# Input_Transceivers.net
KiCad netlist of a schematic drawn in Altium Designer
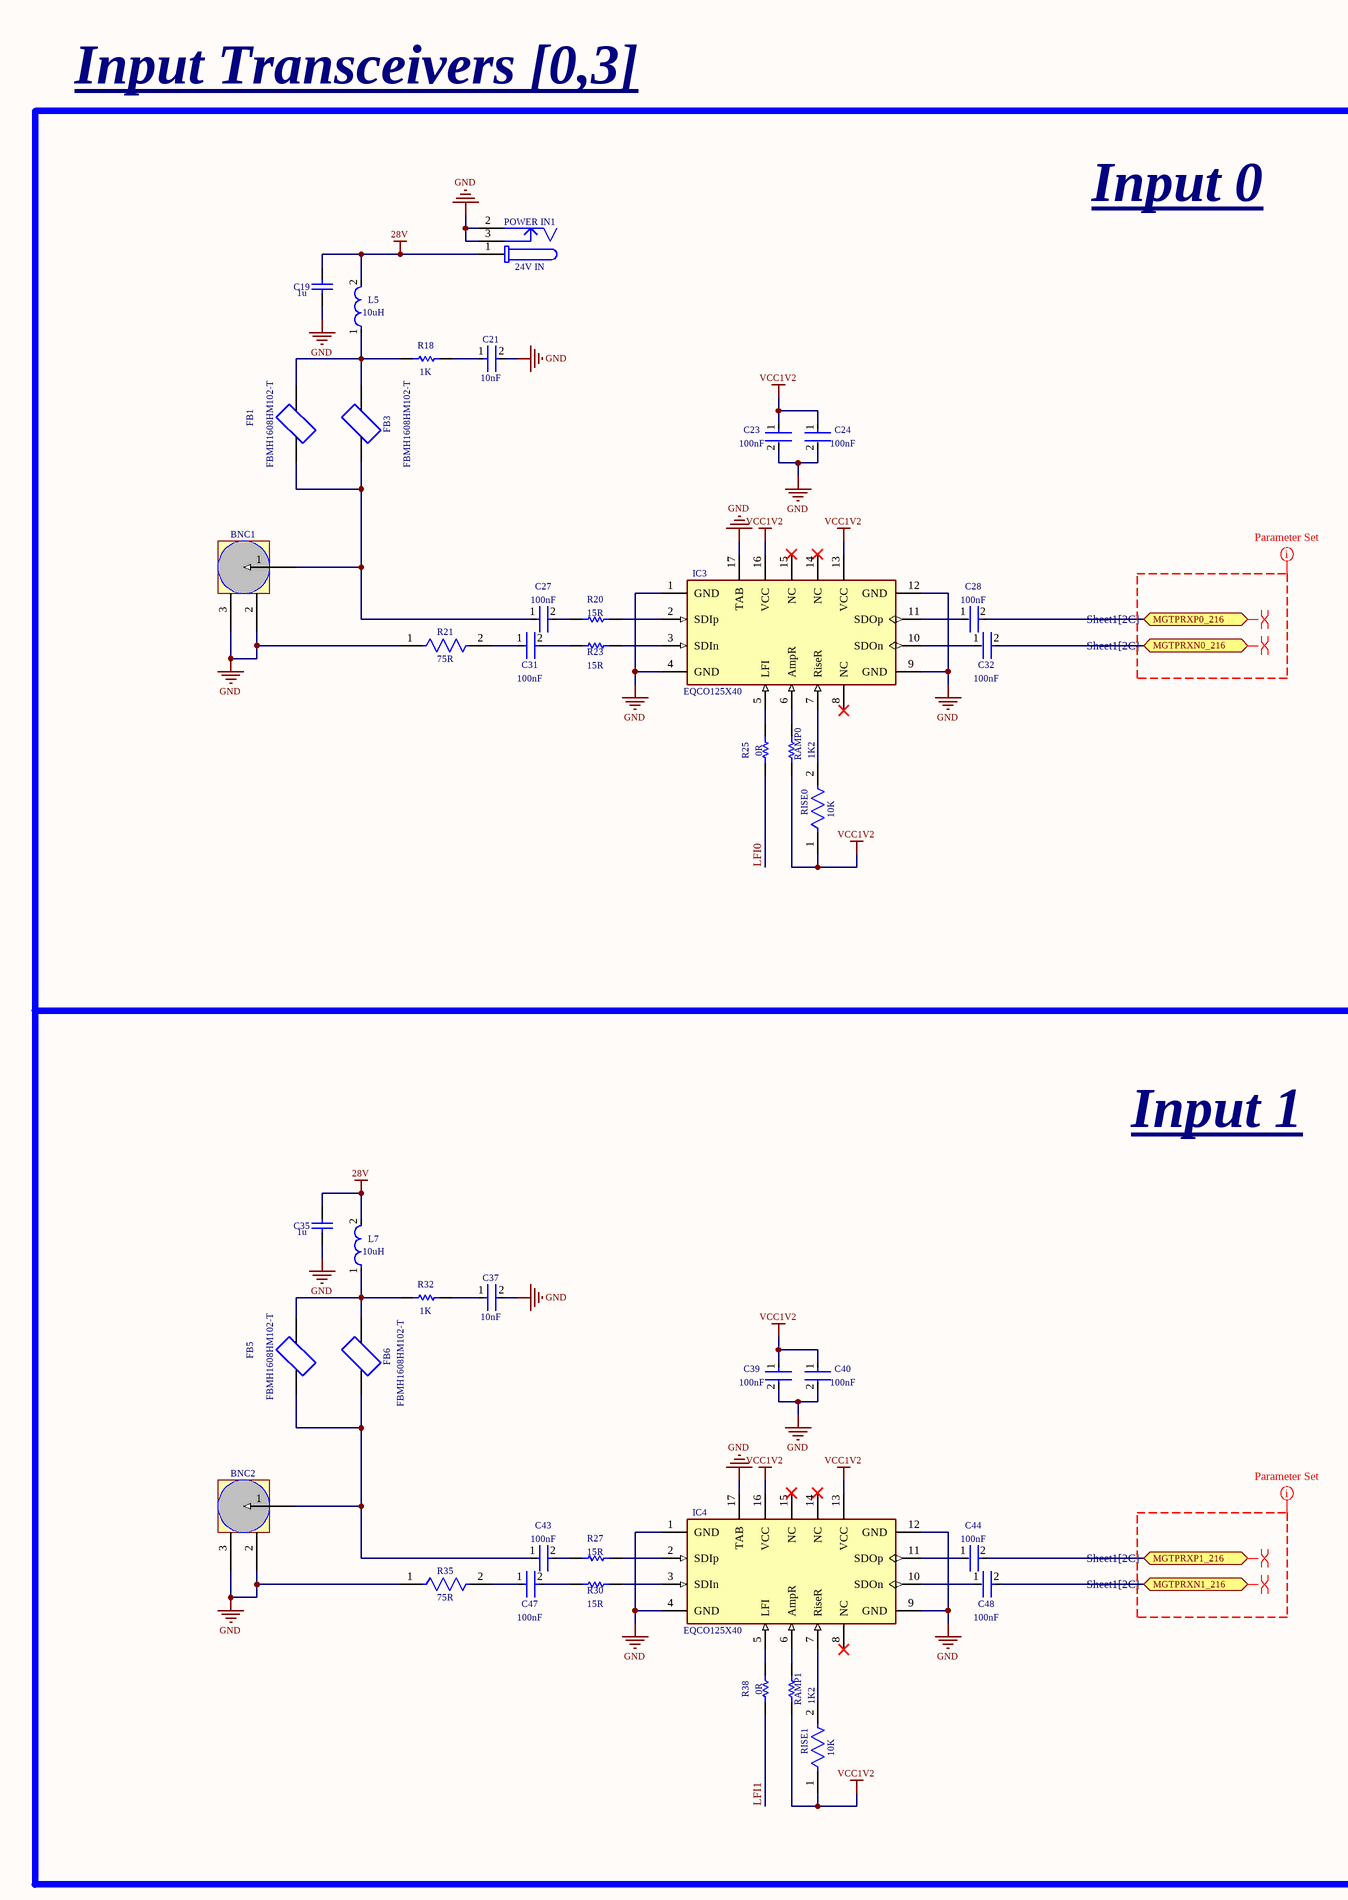
[diagram p0: Input Transceivers.SchDoc, left]
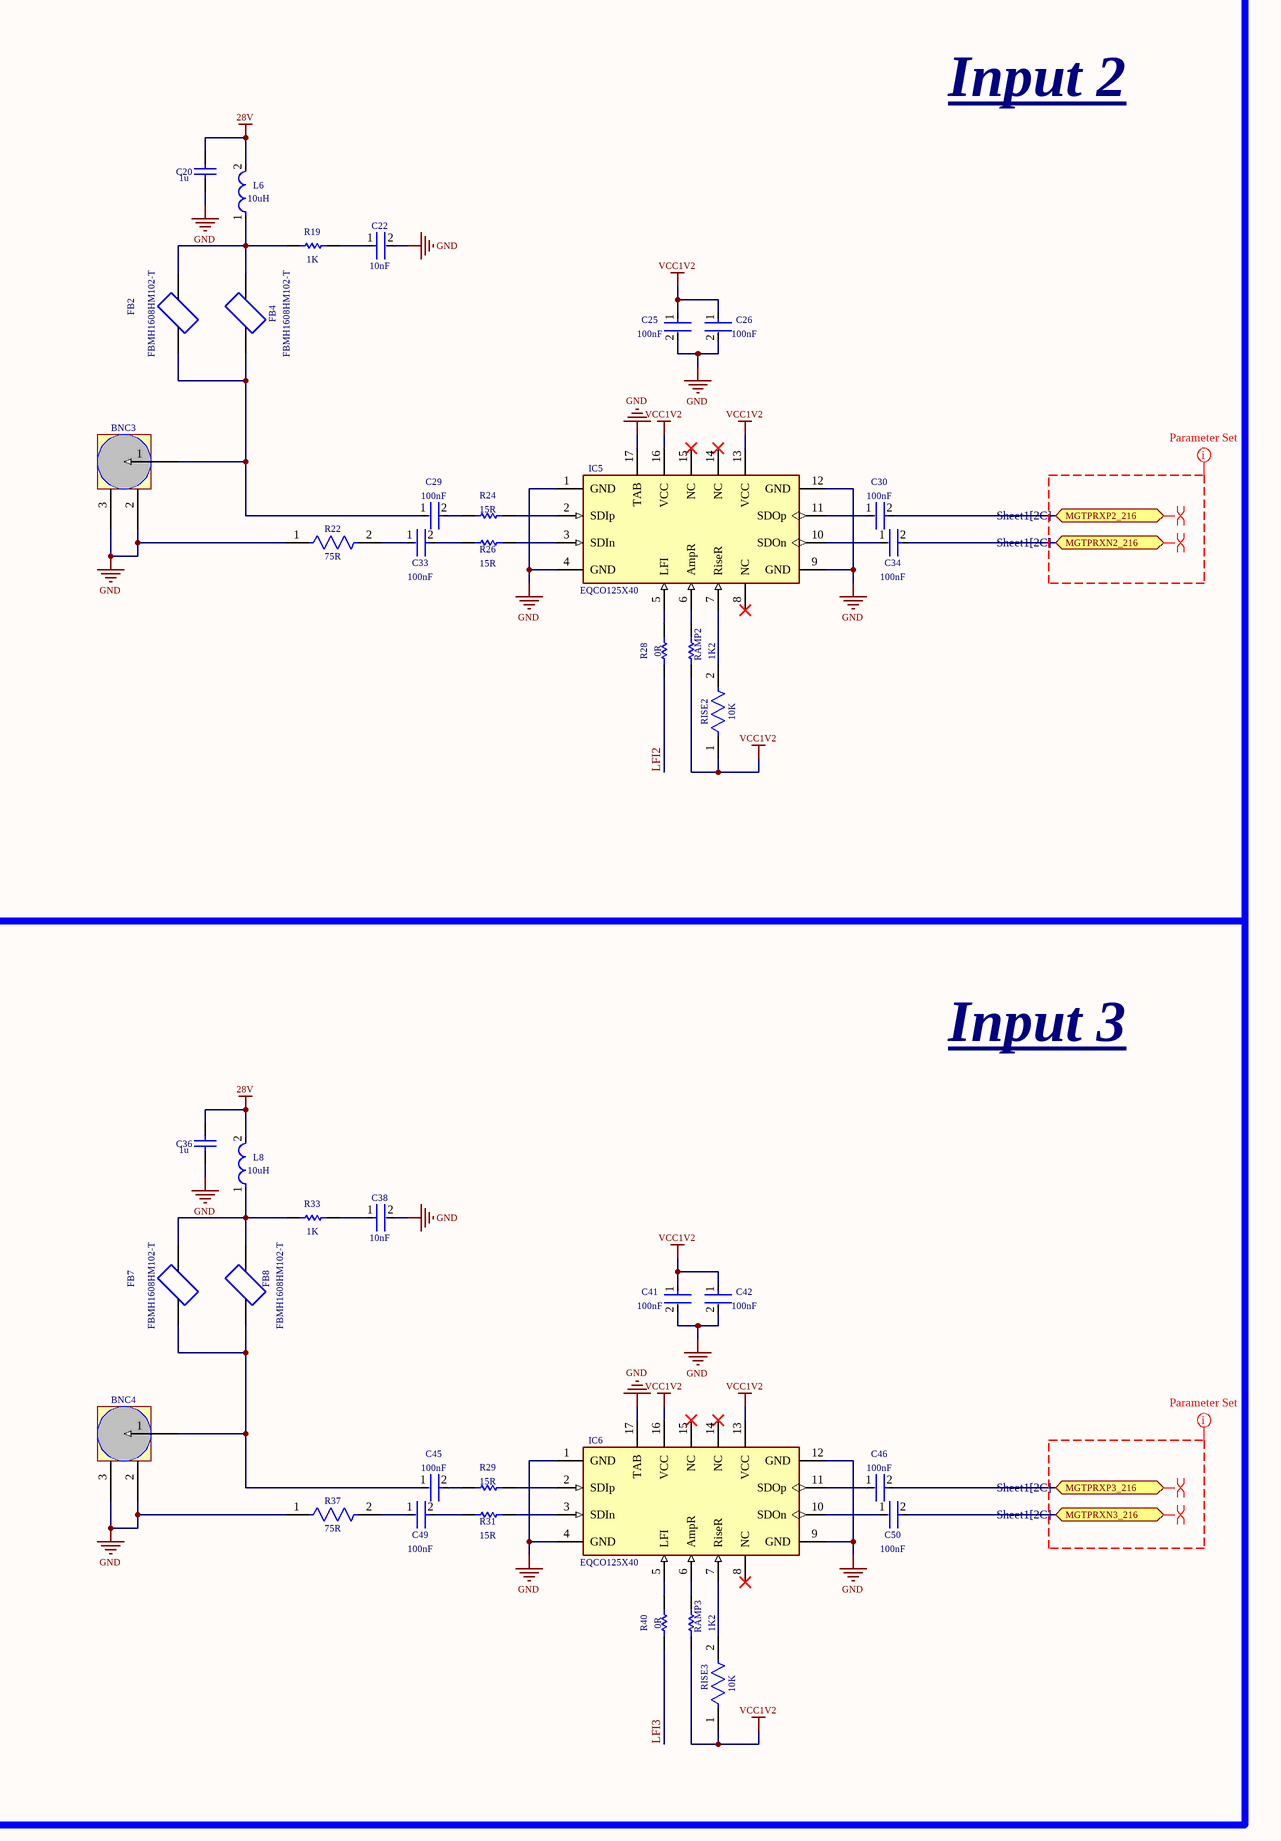
[diagram p1: Input Transceivers.SchDoc, right]

(export (version "E")
  (design (tool "Eeschema 10.0.6"))
  (components
    (comp (ref "BNC1")
      (value "Amphenol_BNC_HD_034_1018")
      (footprint "PCBComponent_1 - duplicate")
      (libsource (lib "Camera_PCB_proj") (part "Component_1_3"))
    )
    (comp (ref "BNC2")
      (value "Amphenol_BNC_HD_034_1018")
      (footprint "PCBComponent_1 - duplicate")
      (libsource (lib "Camera_PCB_proj") (part "Component_1_3"))
    )
    (comp (ref "BNC3")
      (value "Amphenol_BNC_HD_034_1018")
      (footprint "PCBComponent_1 - duplicate")
      (libsource (lib "Camera_PCB_proj") (part "Component_1_3"))
    )
    (comp (ref "BNC4")
      (value "Amphenol_BNC_HD_034_1018")
      (footprint "PCBComponent_1 - duplicate")
      (libsource (lib "Camera_PCB_proj") (part "Component_1_3"))
    )
    (comp (ref "C19")
      (value "1u")
      (footprint "CAPC2013X135X45LL10T25")
      (fields (field (name "MANUFACTURER") "Murata") (field (name "PART NUMBER") "GRM21BR71H105KA12L"))
      (libsource (lib "Altium Content Vault") (part "CAP"))
    )
    (comp (ref "C20")
      (value "1u")
      (footprint "CAPC2013X135X45LL10T25")
      (fields (field (name "MANUFACTURER") "Murata") (field (name "PART NUMBER") "GRM21BR71H105KA12L"))
      (libsource (lib "Altium Content Vault") (part "CAP"))
    )
    (comp (ref "C21")
      (value "10nF")
      (footprint "FP-CL165-IPC_C")
      (description "Cap Ceramic 10nF 50V X7R ±10% SMD 0402 +125°C Paper T/R")
      (fields (field (name "VOLTAGE") "50V") (field (name "TOLERANCE") "10%"))
      (libsource (lib "Altium Content Vault") (part "b4654b650e69147ec39a6b967a45e02"))
    )
    (comp (ref "C22")
      (value "10nF")
      (footprint "FP-CL165-IPC_C")
      (description "Cap Ceramic 10nF 50V X7R ±10% SMD 0402 +125°C Paper T/R")
      (fields (field (name "VOLTAGE") "50V") (field (name "TOLERANCE") "10%"))
      (libsource (lib "Altium Content Vault") (part "b4654b650e69147ec39a6b967a45e02"))
    )
    (comp (ref "C23")
      (value "100nF")
      (footprint "FP-C0402-BB-MFG")
      (description "CAP CER 0.1UF 16V X7R 0402")
      (fields
        (field (name "TOLERANCE") "0.1")
        (field (name "OCTOPART") "https://octopart.com/c0402c104k4ractu-kemet-94158")
      )
      (libsource (lib "Altium Content Vault") (part "b4654b650e69147ec39a6b967a45e02"))
    )
    (comp (ref "C24")
      (value "100nF")
      (footprint "FP-C0402-BB-MFG")
      (description "CAP CER 0.1UF 16V X7R 0402")
      (fields
        (field (name "TOLERANCE") "0.1")
        (field (name "OCTOPART") "https://octopart.com/c0402c104k4ractu-kemet-94158")
      )
      (libsource (lib "Altium Content Vault") (part "b4654b650e69147ec39a6b967a45e02"))
    )
    (comp (ref "C25")
      (value "100nF")
      (footprint "FP-C0402-BB-MFG")
      (description "CAP CER 0.1UF 16V X7R 0402")
      (fields
        (field (name "TOLERANCE") "0.1")
        (field (name "OCTOPART") "https://octopart.com/c0402c104k4ractu-kemet-94158")
      )
      (libsource (lib "Altium Content Vault") (part "b4654b650e69147ec39a6b967a45e02"))
    )
    (comp (ref "C26")
      (value "100nF")
      (footprint "FP-C0402-BB-MFG")
      (description "CAP CER 0.1UF 16V X7R 0402")
      (fields
        (field (name "TOLERANCE") "0.1")
        (field (name "OCTOPART") "https://octopart.com/c0402c104k4ractu-kemet-94158")
      )
      (libsource (lib "Altium Content Vault") (part "b4654b650e69147ec39a6b967a45e02"))
    )
    (comp (ref "C27")
      (value "100nF")
      (footprint "FP-GRM15-MFG")
      (description "CAP CER 0.1UF 16V X7R 0402")
      (fields (field (name "MANUFACTURER PART NUMBER") "GRM155R71C104KA88D") (field (name "TOLERANCE") "10%"))
      (libsource (lib "Altium Content Vault") (part "236180d848d6139a670b325ea6854c9"))
    )
    (comp (ref "C28")
      (value "100nF")
      (footprint "FP-GRM15-MFG")
      (description "CAP CER 0.1UF 16V X7R 0402")
      (fields (field (name "MANUFACTURER PART NUMBER") "GRM155R71C104KA88D") (field (name "TOLERANCE") "10%"))
      (libsource (lib "Altium Content Vault") (part "236180d848d6139a670b325ea6854c9"))
    )
    (comp (ref "C29")
      (value "100nF")
      (footprint "FP-GRM15-MFG")
      (description "CAP CER 0.1UF 16V X7R 0402")
      (fields (field (name "MANUFACTURER PART NUMBER") "GRM155R71C104KA88D") (field (name "TOLERANCE") "10%"))
      (libsource (lib "Altium Content Vault") (part "236180d848d6139a670b325ea6854c9"))
    )
    (comp (ref "C30")
      (value "100nF")
      (footprint "FP-GRM15-MFG")
      (description "CAP CER 0.1UF 16V X7R 0402")
      (fields (field (name "MANUFACTURER PART NUMBER") "GRM155R71C104KA88D") (field (name "TOLERANCE") "10%"))
      (libsource (lib "Altium Content Vault") (part "236180d848d6139a670b325ea6854c9"))
    )
    (comp (ref "C31")
      (value "100nF")
      (footprint "FP-GRM15-MFG")
      (description "CAP CER 0.1UF 16V X7R 0402")
      (fields (field (name "MANUFACTURER PART NUMBER") "GRM155R71C104KA88D") (field (name "TOLERANCE") "10%"))
      (libsource (lib "Altium Content Vault") (part "236180d848d6139a670b325ea6854c9"))
    )
    (comp (ref "C32")
      (value "100nF")
      (footprint "FP-GRM15-MFG")
      (description "CAP CER 0.1UF 16V X7R 0402")
      (fields (field (name "MANUFACTURER PART NUMBER") "GRM155R71C104KA88D") (field (name "TOLERANCE") "10%"))
      (libsource (lib "Altium Content Vault") (part "236180d848d6139a670b325ea6854c9"))
    )
    (comp (ref "C33")
      (value "100nF")
      (footprint "FP-GRM15-MFG")
      (description "CAP CER 0.1UF 16V X7R 0402")
      (fields (field (name "MANUFACTURER PART NUMBER") "GRM155R71C104KA88D") (field (name "TOLERANCE") "10%"))
      (libsource (lib "Altium Content Vault") (part "236180d848d6139a670b325ea6854c9"))
    )
    (comp (ref "C34")
      (value "100nF")
      (footprint "FP-GRM15-MFG")
      (description "CAP CER 0.1UF 16V X7R 0402")
      (fields (field (name "MANUFACTURER PART NUMBER") "GRM155R71C104KA88D") (field (name "TOLERANCE") "10%"))
      (libsource (lib "Altium Content Vault") (part "236180d848d6139a670b325ea6854c9"))
    )
    (comp (ref "C35")
      (value "1u")
      (footprint "CAPC2013X135X45LL10T25")
      (fields (field (name "MANUFACTURER") "Murata") (field (name "PART NUMBER") "GRM21BR71H105KA12L"))
      (libsource (lib "Altium Content Vault") (part "CAP"))
    )
    (comp (ref "C36")
      (value "1u")
      (footprint "CAPC2013X135X45LL10T25")
      (fields (field (name "MANUFACTURER") "Murata") (field (name "PART NUMBER") "GRM21BR71H105KA12L"))
      (libsource (lib "Altium Content Vault") (part "CAP"))
    )
    (comp (ref "C37")
      (value "10nF")
      (footprint "FP-CL165-IPC_C")
      (description "Cap Ceramic 10nF 50V X7R ±10% SMD 0402 +125°C Paper T/R")
      (fields (field (name "VOLTAGE") "50V") (field (name "TOLERANCE") "10%"))
      (libsource (lib "Altium Content Vault") (part "b4654b650e69147ec39a6b967a45e02"))
    )
    (comp (ref "C38")
      (value "10nF")
      (footprint "FP-CL165-IPC_C")
      (description "Cap Ceramic 10nF 50V X7R ±10% SMD 0402 +125°C Paper T/R")
      (fields (field (name "VOLTAGE") "50V") (field (name "TOLERANCE") "10%"))
      (libsource (lib "Altium Content Vault") (part "b4654b650e69147ec39a6b967a45e02"))
    )
    (comp (ref "C39")
      (value "100nF")
      (footprint "FP-C0402-BB-MFG")
      (description "CAP CER 0.1UF 16V X7R 0402")
      (fields
        (field (name "TOLERANCE") "0.1")
        (field (name "OCTOPART") "https://octopart.com/c0402c104k4ractu-kemet-94158")
      )
      (libsource (lib "Altium Content Vault") (part "b4654b650e69147ec39a6b967a45e02"))
    )
    (comp (ref "C40")
      (value "100nF")
      (footprint "FP-C0402-BB-MFG")
      (description "CAP CER 0.1UF 16V X7R 0402")
      (fields
        (field (name "TOLERANCE") "0.1")
        (field (name "OCTOPART") "https://octopart.com/c0402c104k4ractu-kemet-94158")
      )
      (libsource (lib "Altium Content Vault") (part "b4654b650e69147ec39a6b967a45e02"))
    )
    (comp (ref "C41")
      (value "100nF")
      (footprint "FP-C0402-BB-MFG")
      (description "CAP CER 0.1UF 16V X7R 0402")
      (fields
        (field (name "TOLERANCE") "0.1")
        (field (name "OCTOPART") "https://octopart.com/c0402c104k4ractu-kemet-94158")
      )
      (libsource (lib "Altium Content Vault") (part "b4654b650e69147ec39a6b967a45e02"))
    )
    (comp (ref "C42")
      (value "100nF")
      (footprint "FP-C0402-BB-MFG")
      (description "CAP CER 0.1UF 16V X7R 0402")
      (fields
        (field (name "TOLERANCE") "0.1")
        (field (name "OCTOPART") "https://octopart.com/c0402c104k4ractu-kemet-94158")
      )
      (libsource (lib "Altium Content Vault") (part "b4654b650e69147ec39a6b967a45e02"))
    )
    (comp (ref "C43")
      (value "100nF")
      (footprint "FP-GRM15-MFG")
      (description "CAP CER 0.1UF 16V X7R 0402")
      (fields (field (name "MANUFACTURER PART NUMBER") "GRM155R71C104KA88D") (field (name "TOLERANCE") "10%"))
      (libsource (lib "Altium Content Vault") (part "236180d848d6139a670b325ea6854c9"))
    )
    (comp (ref "C44")
      (value "100nF")
      (footprint "FP-GRM15-MFG")
      (description "CAP CER 0.1UF 16V X7R 0402")
      (fields (field (name "MANUFACTURER PART NUMBER") "GRM155R71C104KA88D") (field (name "TOLERANCE") "10%"))
      (libsource (lib "Altium Content Vault") (part "236180d848d6139a670b325ea6854c9"))
    )
    (comp (ref "C45")
      (value "100nF")
      (footprint "FP-GRM15-MFG")
      (description "CAP CER 0.1UF 16V X7R 0402")
      (fields (field (name "MANUFACTURER PART NUMBER") "GRM155R71C104KA88D") (field (name "TOLERANCE") "10%"))
      (libsource (lib "Altium Content Vault") (part "236180d848d6139a670b325ea6854c9"))
    )
    (comp (ref "C46")
      (value "100nF")
      (footprint "FP-GRM15-MFG")
      (description "CAP CER 0.1UF 16V X7R 0402")
      (fields (field (name "MANUFACTURER PART NUMBER") "GRM155R71C104KA88D") (field (name "TOLERANCE") "10%"))
      (libsource (lib "Altium Content Vault") (part "236180d848d6139a670b325ea6854c9"))
    )
    (comp (ref "C47")
      (value "100nF")
      (footprint "FP-GRM15-MFG")
      (description "CAP CER 0.1UF 16V X7R 0402")
      (fields (field (name "MANUFACTURER PART NUMBER") "GRM155R71C104KA88D") (field (name "TOLERANCE") "10%"))
      (libsource (lib "Altium Content Vault") (part "236180d848d6139a670b325ea6854c9"))
    )
    (comp (ref "C48")
      (value "100nF")
      (footprint "FP-GRM15-MFG")
      (description "CAP CER 0.1UF 16V X7R 0402")
      (fields (field (name "MANUFACTURER PART NUMBER") "GRM155R71C104KA88D") (field (name "TOLERANCE") "10%"))
      (libsource (lib "Altium Content Vault") (part "236180d848d6139a670b325ea6854c9"))
    )
    (comp (ref "C49")
      (value "100nF")
      (footprint "FP-GRM15-MFG")
      (description "CAP CER 0.1UF 16V X7R 0402")
      (fields (field (name "MANUFACTURER PART NUMBER") "GRM155R71C104KA88D") (field (name "TOLERANCE") "10%"))
      (libsource (lib "Altium Content Vault") (part "236180d848d6139a670b325ea6854c9"))
    )
    (comp (ref "C50")
      (value "100nF")
      (footprint "FP-GRM15-MFG")
      (description "CAP CER 0.1UF 16V X7R 0402")
      (fields (field (name "MANUFACTURER PART NUMBER") "GRM155R71C104KA88D") (field (name "TOLERANCE") "10%"))
      (libsource (lib "Altium Content Vault") (part "236180d848d6139a670b325ea6854c9"))
    )
    (comp (ref "FB1")
      (value "FBMH1608HM102-T")
      (footprint "PCB_Display_Doru:FBMH1608HM102-T")
      (description "Jumper")
      (fields (field (name "PART_NUMBER") "J00001"))
      (libsource (lib "PCB_Display_Doru") (part "FBMH1608HM102-T"))
    )
    (comp (ref "FB2")
      (value "FBMH1608HM102-T")
      (footprint "PCB_Display_Doru:FBMH1608HM102-T")
      (description "Jumper")
      (fields (field (name "PART_NUMBER") "J00001"))
      (libsource (lib "PCB_Display_Doru") (part "FBMH1608HM102-T"))
    )
    (comp (ref "FB3")
      (value "FBMH1608HM102-T")
      (footprint "PCB_Display_Doru:FBMH1608HM102-T")
      (description "Jumper")
      (fields (field (name "PART_NUMBER") "J00001"))
      (libsource (lib "PCB_Display_Doru") (part "FBMH1608HM102-T"))
    )
    (comp (ref "FB4")
      (value "FBMH1608HM102-T")
      (footprint "PCB_Display_Doru:FBMH1608HM102-T")
      (description "Jumper")
      (fields (field (name "PART_NUMBER") "J00001"))
      (libsource (lib "PCB_Display_Doru") (part "FBMH1608HM102-T"))
    )
    (comp (ref "FB5")
      (value "FBMH1608HM102-T")
      (footprint "PCB_Display_Doru:FBMH1608HM102-T")
      (description "Jumper")
      (fields (field (name "PART_NUMBER") "J00001"))
      (libsource (lib "PCB_Display_Doru") (part "FBMH1608HM102-T"))
    )
    (comp (ref "FB6")
      (value "FBMH1608HM102-T")
      (footprint "PCB_Display_Doru:FBMH1608HM102-T")
      (description "Jumper")
      (fields (field (name "PART_NUMBER") "J00001"))
      (libsource (lib "PCB_Display_Doru") (part "FBMH1608HM102-T"))
    )
    (comp (ref "FB7")
      (value "FBMH1608HM102-T")
      (footprint "PCB_Display_Doru:FBMH1608HM102-T")
      (description "Jumper")
      (fields (field (name "PART_NUMBER") "J00001"))
      (libsource (lib "PCB_Display_Doru") (part "FBMH1608HM102-T"))
    )
    (comp (ref "FB8")
      (value "FBMH1608HM102-T")
      (footprint "PCB_Display_Doru:FBMH1608HM102-T")
      (description "Jumper")
      (fields (field (name "PART_NUMBER") "J00001"))
      (libsource (lib "PCB_Display_Doru") (part "FBMH1608HM102-T"))
    )
    (comp (ref "IC3")
      (value "EQCO125X40")
      (footprint "PCB_Display_Doru:EQCO125X40")
      (description "12.5 Gbps Asymmetric Equalizer/Driver/Repeater")
      (fields (field (name "PART_NUMBER") "J00001"))
      (libsource (lib "PCB_Display_Doru") (part "EQCO125X40"))
    )
    (comp (ref "IC4")
      (value "EQCO125X40")
      (footprint "PCB_Display_Doru:EQCO125X40")
      (description "12.5 Gbps Asymmetric Equalizer/Driver/Repeater")
      (fields (field (name "PART_NUMBER") "J00001"))
      (libsource (lib "PCB_Display_Doru") (part "EQCO125X40"))
    )
    (comp (ref "IC5")
      (value "EQCO125X40")
      (footprint "PCB_Display_Doru:EQCO125X40")
      (description "12.5 Gbps Asymmetric Equalizer/Driver/Repeater")
      (fields (field (name "PART_NUMBER") "J00001"))
      (libsource (lib "PCB_Display_Doru") (part "EQCO125X40"))
    )
    (comp (ref "IC6")
      (value "EQCO125X40")
      (footprint "PCB_Display_Doru:EQCO125X40")
      (description "12.5 Gbps Asymmetric Equalizer/Driver/Repeater")
      (fields (field (name "PART_NUMBER") "J00001"))
      (libsource (lib "PCB_Display_Doru") (part "EQCO125X40"))
    )
    (comp (ref "L5")
      (value "10uH")
      (footprint "FP-1812PS-MFG")
      (description "Fixed Inductors 1812PS Hi SRF Shlded 10uH 5 % 1.7 A")
      (fields (field (name "TOLERANCE") "5%"))
      (libsource (lib "Altium Content Vault") (part "725321dda6339637d4d059423bc1c3c"))
    )
    (comp (ref "L6")
      (value "10uH")
      (footprint "FP-1812PS-MFG")
      (description "Fixed Inductors 1812PS Hi SRF Shlded 10uH 5 % 1.7 A")
      (fields (field (name "TOLERANCE") "5%"))
      (libsource (lib "Altium Content Vault") (part "725321dda6339637d4d059423bc1c3c"))
    )
    (comp (ref "L7")
      (value "10uH")
      (footprint "FP-1812PS-MFG")
      (description "Fixed Inductors 1812PS Hi SRF Shlded 10uH 5 % 1.7 A")
      (fields (field (name "TOLERANCE") "5%"))
      (libsource (lib "Altium Content Vault") (part "725321dda6339637d4d059423bc1c3c"))
    )
    (comp (ref "L8")
      (value "10uH")
      (footprint "FP-1812PS-MFG")
      (description "Fixed Inductors 1812PS Hi SRF Shlded 10uH 5 % 1.7 A")
      (fields (field (name "TOLERANCE") "5%"))
      (libsource (lib "Altium Content Vault") (part "725321dda6339637d4d059423bc1c3c"))
    )
    (comp (ref "POWER IN1")
      (value "24V IN")
      (footprint "694102107102")
      (libsource (lib "Altium Content Vault") (part "DC Power Jack"))
    )
    (comp (ref "R18")
      (value "1K")
      (footprint "RESC1608X55X30LL15T15")
      (fields (field (name "PART NUMBER") "ERJ-3EKF1001V") (field (name "MANUFACTURER") "Panasonic"))
      (libsource (lib "Altium Content Vault") (part "RES"))
    )
    (comp (ref "R19")
      (value "1K")
      (footprint "RESC1608X55X30LL15T15")
      (fields (field (name "PART NUMBER") "ERJ-3EKF1001V") (field (name "MANUFACTURER") "Panasonic"))
      (libsource (lib "Altium Content Vault") (part "RES"))
    )
    (comp (ref "R20")
      (value "15R")
      (footprint "RESC1005X40X25ML10T10")
      (fields (field (name "MANUFACTURER") "Multicomp") (field (name "PART NUMBER") "MC00625W0402115R"))
      (libsource (lib "Altium Content Vault") (part "RES"))
    )
    (comp (ref "R21")
      (value "75R")
      (footprint "FP-ERJ2RK-IPC_B")
      (description "RES SMD 75 OHM 1% 1/10W 0402")
      (fields (field (name "TOLERANCE") "1%"))
      (libsource (lib "Altium Content Vault") (part "1029c3af85768c4190bb7ad29bc67b5"))
    )
    (comp (ref "R22")
      (value "75R")
      (footprint "FP-ERJ2RK-IPC_B")
      (description "RES SMD 75 OHM 1% 1/10W 0402")
      (fields (field (name "TOLERANCE") "1%"))
      (libsource (lib "Altium Content Vault") (part "1029c3af85768c4190bb7ad29bc67b5"))
    )
    (comp (ref "R23")
      (value "15R")
      (footprint "RESC1005X40X25ML10T10")
      (fields (field (name "MANUFACTURER") "Multicomp") (field (name "PART NUMBER") "MC00625W0402115R"))
      (libsource (lib "Altium Content Vault") (part "RES"))
    )
    (comp (ref "R24")
      (value "15R")
      (footprint "RESC1005X40X25ML10T10")
      (fields (field (name "MANUFACTURER") "Multicomp") (field (name "PART NUMBER") "MC00625W0402115R"))
      (libsource (lib "Altium Content Vault") (part "RES"))
    )
    (comp (ref "R25")
      (value "0R")
      (footprint "RESC1005X40X25NL05T10")
      (fields (field (name "MANUFACTURER") "Yageo / Phycomp") (field (name "PART NUMBER") "RC0402JR-070RL"))
      (libsource (lib "Altium Content Vault") (part "RES"))
    )
    (comp (ref "R26")
      (value "15R")
      (footprint "RESC1005X40X25ML10T10")
      (fields (field (name "MANUFACTURER") "Multicomp") (field (name "PART NUMBER") "MC00625W0402115R"))
      (libsource (lib "Altium Content Vault") (part "RES"))
    )
    (comp (ref "R27")
      (value "15R")
      (footprint "RESC1005X40X25ML10T10")
      (fields (field (name "MANUFACTURER") "Multicomp") (field (name "PART NUMBER") "MC00625W0402115R"))
      (libsource (lib "Altium Content Vault") (part "RES"))
    )
    (comp (ref "R28")
      (value "0R")
      (footprint "RESC1005X40X25NL05T10")
      (fields (field (name "MANUFACTURER") "Yageo / Phycomp") (field (name "PART NUMBER") "RC0402JR-070RL"))
      (libsource (lib "Altium Content Vault") (part "RES"))
    )
    (comp (ref "R29")
      (value "15R")
      (footprint "RESC1005X40X25ML10T10")
      (fields (field (name "MANUFACTURER") "Multicomp") (field (name "PART NUMBER") "MC00625W0402115R"))
      (libsource (lib "Altium Content Vault") (part "RES"))
    )
    (comp (ref "R30")
      (value "15R")
      (footprint "RESC1005X40X25ML10T10")
      (fields (field (name "MANUFACTURER") "Multicomp") (field (name "PART NUMBER") "MC00625W0402115R"))
      (libsource (lib "Altium Content Vault") (part "RES"))
    )
    (comp (ref "R31")
      (value "15R")
      (footprint "RESC1005X40X25ML10T10")
      (fields (field (name "MANUFACTURER") "Multicomp") (field (name "PART NUMBER") "MC00625W0402115R"))
      (libsource (lib "Altium Content Vault") (part "RES"))
    )
    (comp (ref "R32")
      (value "1K")
      (footprint "RESC1608X55X30LL15T15")
      (fields (field (name "PART NUMBER") "ERJ-3EKF1001V") (field (name "MANUFACTURER") "Panasonic"))
      (libsource (lib "Altium Content Vault") (part "RES"))
    )
    (comp (ref "R33")
      (value "1K")
      (footprint "RESC1608X55X30LL15T15")
      (fields (field (name "PART NUMBER") "ERJ-3EKF1001V") (field (name "MANUFACTURER") "Panasonic"))
      (libsource (lib "Altium Content Vault") (part "RES"))
    )
    (comp (ref "R35")
      (value "75R")
      (footprint "FP-ERJ2RK-IPC_B")
      (description "RES SMD 75 OHM 1% 1/10W 0402")
      (fields (field (name "TOLERANCE") "1%"))
      (libsource (lib "Altium Content Vault") (part "1029c3af85768c4190bb7ad29bc67b5"))
    )
    (comp (ref "R37")
      (value "75R")
      (footprint "FP-ERJ2RK-IPC_B")
      (description "RES SMD 75 OHM 1% 1/10W 0402")
      (fields (field (name "TOLERANCE") "1%"))
      (libsource (lib "Altium Content Vault") (part "1029c3af85768c4190bb7ad29bc67b5"))
    )
    (comp (ref "R38")
      (value "0R")
      (footprint "RESC1005X40X25NL05T10")
      (fields (field (name "MANUFACTURER") "Yageo / Phycomp") (field (name "PART NUMBER") "RC0402JR-070RL"))
      (libsource (lib "Altium Content Vault") (part "RES"))
    )
    (comp (ref "R40")
      (value "0R")
      (footprint "RESC1005X40X25NL05T10")
      (fields (field (name "MANUFACTURER") "Yageo / Phycomp") (field (name "PART NUMBER") "RC0402JR-070RL"))
      (libsource (lib "Altium Content Vault") (part "RES"))
    )
    (comp (ref "RAMP0")
      (value "1K2")
      (footprint "RESC1608X55X25LL10T15")
      (description "Chip Resistor, 1.2 KOhm, +/- 1%, 0.1 W, -55 to 155 degC, 0603 (1608 Metric), RoHS, Tape and Reel")
      (fields (field (name "TOLERANCE") "1%"))
      (libsource (lib "Altium Content Vault") (part "RES-2"))
    )
    (comp (ref "RAMP1")
      (value "1K2")
      (footprint "RESC1608X55X25LL10T15")
      (description "Chip Resistor, 1.2 KOhm, +/- 1%, 0.1 W, -55 to 155 degC, 0603 (1608 Metric), RoHS, Tape and Reel")
      (fields (field (name "TOLERANCE") "1%"))
      (libsource (lib "Altium Content Vault") (part "RES-2"))
    )
    (comp (ref "RAMP2")
      (value "1K2")
      (footprint "RESC1608X55X25LL10T15")
      (description "Chip Resistor, 1.2 KOhm, +/- 1%, 0.1 W, -55 to 155 degC, 0603 (1608 Metric), RoHS, Tape and Reel")
      (fields (field (name "TOLERANCE") "1%"))
      (libsource (lib "Altium Content Vault") (part "RES-2"))
    )
    (comp (ref "RAMP3")
      (value "1K2")
      (footprint "RESC1608X55X25LL10T15")
      (description "Chip Resistor, 1.2 KOhm, +/- 1%, 0.1 W, -55 to 155 degC, 0603 (1608 Metric), RoHS, Tape and Reel")
      (fields (field (name "TOLERANCE") "1%"))
      (libsource (lib "Altium Content Vault") (part "RES-2"))
    )
    (comp (ref "RISE0")
      (value "10K")
      (footprint "FP-RC0603-0_55-IPC_C")
      (description "RES 10K OHM 1% 1/10W 0603")
      (fields (field (name "TOLERANCE") "1%"))
      (libsource (lib "Altium Content Vault") (part "1029c3af85768c4190bb7ad29bc67b5"))
    )
    (comp (ref "RISE1")
      (value "10K")
      (footprint "FP-RC0603-0_55-IPC_C")
      (description "RES 10K OHM 1% 1/10W 0603")
      (fields (field (name "TOLERANCE") "1%"))
      (libsource (lib "Altium Content Vault") (part "1029c3af85768c4190bb7ad29bc67b5"))
    )
    (comp (ref "RISE2")
      (value "10K")
      (footprint "FP-RC0603-0_55-IPC_C")
      (description "RES 10K OHM 1% 1/10W 0603")
      (fields (field (name "TOLERANCE") "1%"))
      (libsource (lib "Altium Content Vault") (part "1029c3af85768c4190bb7ad29bc67b5"))
    )
    (comp (ref "RISE3")
      (value "10K")
      (footprint "FP-RC0603-0_55-IPC_C")
      (description "RES 10K OHM 1% 1/10W 0603")
      (fields (field (name "TOLERANCE") "1%"))
      (libsource (lib "Altium Content Vault") (part "1029c3af85768c4190bb7ad29bc67b5"))
    )
  )
  (nets
    (net (code "1") (name "/LFI0") (class "Default")
      (node (ref "R25") (pin "1") (pinfunction "1_1") (pintype "passive"))
    )
    (net (code "2") (name "/LFI1") (class "Default")
      (node (ref "R38") (pin "1") (pinfunction "1_1") (pintype "passive"))
    )
    (net (code "3") (name "/LFI2") (class "Default")
      (node (ref "R28") (pin "1") (pinfunction "1_1") (pintype "passive"))
    )
    (net (code "4") (name "/LFI3") (class "Default")
      (node (ref "R40") (pin "1") (pinfunction "1_1") (pintype "passive"))
    )
    (net (code "5") (name "/MGTPRXN0_216") (class "Default")
      (node (ref "C32") (pin "2") (pinfunction "2_2") (pintype "passive"))
    )
    (net (code "6") (name "/MGTPRXN1_216") (class "Default")
      (node (ref "C48") (pin "2") (pinfunction "2_2") (pintype "passive"))
    )
    (net (code "7") (name "/MGTPRXN2_216") (class "Default")
      (node (ref "C34") (pin "2") (pinfunction "2_2") (pintype "passive"))
    )
    (net (code "8") (name "/MGTPRXN3_216") (class "Default")
      (node (ref "C50") (pin "2") (pinfunction "2_2") (pintype "passive"))
    )
    (net (code "9") (name "/MGTPRXP0_216") (class "Default")
      (node (ref "C28") (pin "2") (pinfunction "2_2") (pintype "passive"))
    )
    (net (code "10") (name "/MGTPRXP1_216") (class "Default")
      (node (ref "C44") (pin "2") (pinfunction "2_2") (pintype "passive"))
    )
    (net (code "11") (name "/MGTPRXP2_216") (class "Default")
      (node (ref "C30") (pin "2") (pinfunction "2_2") (pintype "passive"))
    )
    (net (code "12") (name "/MGTPRXP3_216") (class "Default")
      (node (ref "C46") (pin "2") (pinfunction "2_2") (pintype "passive"))
    )
    (net (code "13") (name "28V") (class "Default")
      (node (ref "C19") (pin "2") (pinfunction "2_2") (pintype "passive"))
      (node (ref "C20") (pin "2") (pinfunction "2_2") (pintype "passive"))
      (node (ref "C35") (pin "2") (pinfunction "2_2") (pintype "passive"))
      (node (ref "C36") (pin "2") (pinfunction "2_2") (pintype "passive"))
      (node (ref "L5") (pin "2") (pinfunction "2_2") (pintype "passive"))
      (node (ref "L6") (pin "2") (pinfunction "2_2") (pintype "passive"))
      (node (ref "L7") (pin "2") (pinfunction "2_2") (pintype "passive"))
      (node (ref "L8") (pin "2") (pinfunction "2_2") (pintype "passive"))
      (node (ref "POWER IN1") (pin "1") (pinfunction "1_1") (pintype "passive"))
    )
    (net (code "14") (name "GND") (class "Default")
      (node (ref "BNC1") (pin "2") (pintype "passive"))
      (node (ref "BNC1") (pin "3") (pintype "passive"))
      (node (ref "BNC2") (pin "2") (pintype "passive"))
      (node (ref "BNC2") (pin "3") (pintype "passive"))
      (node (ref "BNC3") (pin "2") (pintype "passive"))
      (node (ref "BNC3") (pin "3") (pintype "passive"))
      (node (ref "BNC4") (pin "2") (pintype "passive"))
      (node (ref "BNC4") (pin "3") (pintype "passive"))
      (node (ref "C19") (pin "1") (pinfunction "1_1") (pintype "passive"))
      (node (ref "C20") (pin "1") (pinfunction "1_1") (pintype "passive"))
      (node (ref "C21") (pin "2") (pinfunction "2_2") (pintype "passive"))
      (node (ref "C22") (pin "2") (pinfunction "2_2") (pintype "passive"))
      (node (ref "C23") (pin "2") (pinfunction "2_2") (pintype "passive"))
      (node (ref "C24") (pin "2") (pinfunction "2_2") (pintype "passive"))
      (node (ref "C25") (pin "2") (pinfunction "2_2") (pintype "passive"))
      (node (ref "C26") (pin "2") (pinfunction "2_2") (pintype "passive"))
      (node (ref "C35") (pin "1") (pinfunction "1_1") (pintype "passive"))
      (node (ref "C36") (pin "1") (pinfunction "1_1") (pintype "passive"))
      (node (ref "C37") (pin "2") (pinfunction "2_2") (pintype "passive"))
      (node (ref "C38") (pin "2") (pinfunction "2_2") (pintype "passive"))
      (node (ref "C39") (pin "2") (pinfunction "2_2") (pintype "passive"))
      (node (ref "C40") (pin "2") (pinfunction "2_2") (pintype "passive"))
      (node (ref "C41") (pin "2") (pinfunction "2_2") (pintype "passive"))
      (node (ref "C42") (pin "2") (pinfunction "2_2") (pintype "passive"))
      (node (ref "IC3") (pin "1") (pinfunction "GND_1") (pintype "power_in"))
      (node (ref "IC3") (pin "12") (pinfunction "GND_12") (pintype "power_in"))
      (node (ref "IC3") (pin "17") (pinfunction "TAB_17") (pintype "power_in"))
      (node (ref "IC3") (pin "4") (pinfunction "GND_4") (pintype "power_in"))
      (node (ref "IC3") (pin "9") (pinfunction "GND_9") (pintype "power_in"))
      (node (ref "IC4") (pin "1") (pinfunction "GND_1") (pintype "power_in"))
      (node (ref "IC4") (pin "12") (pinfunction "GND_12") (pintype "power_in"))
      (node (ref "IC4") (pin "17") (pinfunction "TAB_17") (pintype "power_in"))
      (node (ref "IC4") (pin "4") (pinfunction "GND_4") (pintype "power_in"))
      (node (ref "IC4") (pin "9") (pinfunction "GND_9") (pintype "power_in"))
      (node (ref "IC5") (pin "1") (pinfunction "GND_1") (pintype "power_in"))
      (node (ref "IC5") (pin "12") (pinfunction "GND_12") (pintype "power_in"))
      (node (ref "IC5") (pin "17") (pinfunction "TAB_17") (pintype "power_in"))
      (node (ref "IC5") (pin "4") (pinfunction "GND_4") (pintype "power_in"))
      (node (ref "IC5") (pin "9") (pinfunction "GND_9") (pintype "power_in"))
      (node (ref "IC6") (pin "1") (pinfunction "GND_1") (pintype "power_in"))
      (node (ref "IC6") (pin "12") (pinfunction "GND_12") (pintype "power_in"))
      (node (ref "IC6") (pin "17") (pinfunction "TAB_17") (pintype "power_in"))
      (node (ref "IC6") (pin "4") (pinfunction "GND_4") (pintype "power_in"))
      (node (ref "IC6") (pin "9") (pinfunction "GND_9") (pintype "power_in"))
      (node (ref "POWER IN1") (pin "2") (pinfunction "2_2") (pintype "passive"))
      (node (ref "POWER IN1") (pin "3") (pinfunction "3_3") (pintype "passive"))
      (node (ref "R21") (pin "1") (pinfunction "1_1") (pintype "passive"))
      (node (ref "R22") (pin "1") (pinfunction "1_1") (pintype "passive"))
      (node (ref "R35") (pin "1") (pinfunction "1_1") (pintype "passive"))
      (node (ref "R37") (pin "1") (pinfunction "1_1") (pintype "passive"))
    )
    (net (code "15") (name "Net-(BNC1-Pad1)") (class "Default")
      (node (ref "BNC1") (pin "1") (pintype "input"))
      (node (ref "C27") (pin "1") (pinfunction "1_1") (pintype "passive"))
      (node (ref "FB1") (pin "1") (pinfunction "1_1") (pintype "passive"))
      (node (ref "FB3") (pin "1") (pinfunction "1_1") (pintype "passive"))
    )
    (net (code "16") (name "Net-(BNC2-Pad1)") (class "Default")
      (node (ref "BNC2") (pin "1") (pintype "input"))
      (node (ref "C43") (pin "1") (pinfunction "1_1") (pintype "passive"))
      (node (ref "FB5") (pin "1") (pinfunction "1_1") (pintype "passive"))
      (node (ref "FB6") (pin "1") (pinfunction "1_1") (pintype "passive"))
    )
    (net (code "17") (name "Net-(BNC3-Pad1)") (class "Default")
      (node (ref "BNC3") (pin "1") (pintype "input"))
      (node (ref "C29") (pin "1") (pinfunction "1_1") (pintype "passive"))
      (node (ref "FB2") (pin "1") (pinfunction "1_1") (pintype "passive"))
      (node (ref "FB4") (pin "1") (pinfunction "1_1") (pintype "passive"))
    )
    (net (code "18") (name "Net-(BNC4-Pad1)") (class "Default")
      (node (ref "BNC4") (pin "1") (pintype "input"))
      (node (ref "C45") (pin "1") (pinfunction "1_1") (pintype "passive"))
      (node (ref "FB7") (pin "1") (pinfunction "1_1") (pintype "passive"))
      (node (ref "FB8") (pin "1") (pinfunction "1_1") (pintype "passive"))
    )
    (net (code "19") (name "Net-(C21-Pad1)") (class "Default")
      (node (ref "C21") (pin "1") (pinfunction "1_1") (pintype "passive"))
      (node (ref "R18") (pin "2") (pinfunction "2_2") (pintype "passive"))
    )
    (net (code "20") (name "Net-(C22-Pad1)") (class "Default")
      (node (ref "C22") (pin "1") (pinfunction "1_1") (pintype "passive"))
      (node (ref "R19") (pin "2") (pinfunction "2_2") (pintype "passive"))
    )
    (net (code "21") (name "Net-(C27-Pad2)") (class "Default")
      (node (ref "C27") (pin "2") (pinfunction "2_2") (pintype "passive"))
      (node (ref "R20") (pin "1") (pinfunction "1_1") (pintype "passive"))
    )
    (net (code "22") (name "Net-(C29-Pad2)") (class "Default")
      (node (ref "C29") (pin "2") (pinfunction "2_2") (pintype "passive"))
      (node (ref "R24") (pin "1") (pinfunction "1_1") (pintype "passive"))
    )
    (net (code "23") (name "Net-(C31-Pad1)") (class "Default")
      (node (ref "C31") (pin "1") (pinfunction "1_1") (pintype "passive"))
      (node (ref "R21") (pin "2") (pinfunction "2_2") (pintype "passive"))
    )
    (net (code "24") (name "Net-(C31-Pad2)") (class "Default")
      (node (ref "C31") (pin "2") (pinfunction "2_2") (pintype "passive"))
      (node (ref "R23") (pin "1") (pinfunction "1_1") (pintype "passive"))
    )
    (net (code "25") (name "Net-(C33-Pad1)") (class "Default")
      (node (ref "C33") (pin "1") (pinfunction "1_1") (pintype "passive"))
      (node (ref "R22") (pin "2") (pinfunction "2_2") (pintype "passive"))
    )
    (net (code "26") (name "Net-(C33-Pad2)") (class "Default")
      (node (ref "C33") (pin "2") (pinfunction "2_2") (pintype "passive"))
      (node (ref "R26") (pin "1") (pinfunction "1_1") (pintype "passive"))
    )
    (net (code "27") (name "Net-(C37-Pad1)") (class "Default")
      (node (ref "C37") (pin "1") (pinfunction "1_1") (pintype "passive"))
      (node (ref "R32") (pin "2") (pinfunction "2_2") (pintype "passive"))
    )
    (net (code "28") (name "Net-(C38-Pad1)") (class "Default")
      (node (ref "C38") (pin "1") (pinfunction "1_1") (pintype "passive"))
      (node (ref "R33") (pin "2") (pinfunction "2_2") (pintype "passive"))
    )
    (net (code "29") (name "Net-(C43-Pad2)") (class "Default")
      (node (ref "C43") (pin "2") (pinfunction "2_2") (pintype "passive"))
      (node (ref "R27") (pin "1") (pinfunction "1_1") (pintype "passive"))
    )
    (net (code "30") (name "Net-(C45-Pad2)") (class "Default")
      (node (ref "C45") (pin "2") (pinfunction "2_2") (pintype "passive"))
      (node (ref "R29") (pin "1") (pinfunction "1_1") (pintype "passive"))
    )
    (net (code "31") (name "Net-(C47-Pad1)") (class "Default")
      (node (ref "C47") (pin "1") (pinfunction "1_1") (pintype "passive"))
      (node (ref "R35") (pin "2") (pinfunction "2_2") (pintype "passive"))
    )
    (net (code "32") (name "Net-(C47-Pad2)") (class "Default")
      (node (ref "C47") (pin "2") (pinfunction "2_2") (pintype "passive"))
      (node (ref "R30") (pin "1") (pinfunction "1_1") (pintype "passive"))
    )
    (net (code "33") (name "Net-(C49-Pad1)") (class "Default")
      (node (ref "C49") (pin "1") (pinfunction "1_1") (pintype "passive"))
      (node (ref "R37") (pin "2") (pinfunction "2_2") (pintype "passive"))
    )
    (net (code "34") (name "Net-(C49-Pad2)") (class "Default")
      (node (ref "C49") (pin "2") (pinfunction "2_2") (pintype "passive"))
      (node (ref "R31") (pin "1") (pinfunction "1_1") (pintype "passive"))
    )
    (net (code "35") (name "Net-(FB1-Pad2)") (class "Default")
      (node (ref "FB1") (pin "2") (pinfunction "2_2") (pintype "passive"))
      (node (ref "FB3") (pin "2") (pinfunction "2_2") (pintype "passive"))
      (node (ref "L5") (pin "1") (pinfunction "1_1") (pintype "passive"))
      (node (ref "R18") (pin "1") (pinfunction "1_1") (pintype "passive"))
    )
    (net (code "36") (name "Net-(FB2-Pad2)") (class "Default")
      (node (ref "FB2") (pin "2") (pinfunction "2_2") (pintype "passive"))
      (node (ref "FB4") (pin "2") (pinfunction "2_2") (pintype "passive"))
      (node (ref "L6") (pin "1") (pinfunction "1_1") (pintype "passive"))
      (node (ref "R19") (pin "1") (pinfunction "1_1") (pintype "passive"))
    )
    (net (code "37") (name "Net-(FB5-Pad2)") (class "Default")
      (node (ref "FB5") (pin "2") (pinfunction "2_2") (pintype "passive"))
      (node (ref "FB6") (pin "2") (pinfunction "2_2") (pintype "passive"))
      (node (ref "L7") (pin "1") (pinfunction "1_1") (pintype "passive"))
      (node (ref "R32") (pin "1") (pinfunction "1_1") (pintype "passive"))
    )
    (net (code "38") (name "Net-(FB7-Pad2)") (class "Default")
      (node (ref "FB7") (pin "2") (pinfunction "2_2") (pintype "passive"))
      (node (ref "FB8") (pin "2") (pinfunction "2_2") (pintype "passive"))
      (node (ref "L8") (pin "1") (pinfunction "1_1") (pintype "passive"))
      (node (ref "R33") (pin "1") (pinfunction "1_1") (pintype "passive"))
    )
    (net (code "39") (name "Net-(IC3-AmpR)") (class "Default")
      (node (ref "IC3") (pin "6") (pinfunction "AmpR_6") (pintype "input"))
      (node (ref "RAMP0") (pin "2") (pinfunction "2_2") (pintype "passive"))
    )
    (net (code "40") (name "Net-(IC3-LFI)") (class "Default")
      (node (ref "IC3") (pin "5") (pinfunction "LFI_5") (pintype "input"))
      (node (ref "R25") (pin "2") (pinfunction "2_2") (pintype "passive"))
    )
    (net (code "41") (name "Net-(IC3-RiseR)") (class "Default")
      (node (ref "IC3") (pin "7") (pinfunction "RiseR_7") (pintype "input"))
      (node (ref "RISE0") (pin "2") (pinfunction "2_2") (pintype "passive"))
    )
    (net (code "42") (name "Net-(IC3-SDIn)") (class "Default")
      (node (ref "IC3") (pin "3") (pinfunction "SDIn_3") (pintype "input"))
      (node (ref "R23") (pin "2") (pinfunction "2_2") (pintype "passive"))
    )
    (net (code "43") (name "Net-(IC3-SDIp)") (class "Default")
      (node (ref "IC3") (pin "2") (pinfunction "SDIp_2") (pintype "input"))
      (node (ref "R20") (pin "2") (pinfunction "2_2") (pintype "passive"))
    )
    (net (code "44") (name "Net-(IC3-SDOn)") (class "Default")
      (node (ref "C32") (pin "1") (pinfunction "1_1") (pintype "passive"))
      (node (ref "IC3") (pin "10") (pinfunction "SDOn_10") (pintype "output"))
    )
    (net (code "45") (name "Net-(IC3-SDOp)") (class "Default")
      (node (ref "C28") (pin "1") (pinfunction "1_1") (pintype "passive"))
      (node (ref "IC3") (pin "11") (pinfunction "SDOp_11") (pintype "output"))
    )
    (net (code "46") (name "Net-(IC4-AmpR)") (class "Default")
      (node (ref "IC4") (pin "6") (pinfunction "AmpR_6") (pintype "input"))
      (node (ref "RAMP1") (pin "2") (pinfunction "2_2") (pintype "passive"))
    )
    (net (code "47") (name "Net-(IC4-LFI)") (class "Default")
      (node (ref "IC4") (pin "5") (pinfunction "LFI_5") (pintype "input"))
      (node (ref "R38") (pin "2") (pinfunction "2_2") (pintype "passive"))
    )
    (net (code "48") (name "Net-(IC4-RiseR)") (class "Default")
      (node (ref "IC4") (pin "7") (pinfunction "RiseR_7") (pintype "input"))
      (node (ref "RISE1") (pin "2") (pinfunction "2_2") (pintype "passive"))
    )
    (net (code "49") (name "Net-(IC4-SDIn)") (class "Default")
      (node (ref "IC4") (pin "3") (pinfunction "SDIn_3") (pintype "input"))
      (node (ref "R30") (pin "2") (pinfunction "2_2") (pintype "passive"))
    )
    (net (code "50") (name "Net-(IC4-SDIp)") (class "Default")
      (node (ref "IC4") (pin "2") (pinfunction "SDIp_2") (pintype "input"))
      (node (ref "R27") (pin "2") (pinfunction "2_2") (pintype "passive"))
    )
    (net (code "51") (name "Net-(IC4-SDOn)") (class "Default")
      (node (ref "C48") (pin "1") (pinfunction "1_1") (pintype "passive"))
      (node (ref "IC4") (pin "10") (pinfunction "SDOn_10") (pintype "output"))
    )
    (net (code "52") (name "Net-(IC4-SDOp)") (class "Default")
      (node (ref "C44") (pin "1") (pinfunction "1_1") (pintype "passive"))
      (node (ref "IC4") (pin "11") (pinfunction "SDOp_11") (pintype "output"))
    )
    (net (code "53") (name "Net-(IC5-AmpR)") (class "Default")
      (node (ref "IC5") (pin "6") (pinfunction "AmpR_6") (pintype "input"))
      (node (ref "RAMP2") (pin "2") (pinfunction "2_2") (pintype "passive"))
    )
    (net (code "54") (name "Net-(IC5-LFI)") (class "Default")
      (node (ref "IC5") (pin "5") (pinfunction "LFI_5") (pintype "input"))
      (node (ref "R28") (pin "2") (pinfunction "2_2") (pintype "passive"))
    )
    (net (code "55") (name "Net-(IC5-RiseR)") (class "Default")
      (node (ref "IC5") (pin "7") (pinfunction "RiseR_7") (pintype "input"))
      (node (ref "RISE2") (pin "2") (pinfunction "2_2") (pintype "passive"))
    )
    (net (code "56") (name "Net-(IC5-SDIn)") (class "Default")
      (node (ref "IC5") (pin "3") (pinfunction "SDIn_3") (pintype "input"))
      (node (ref "R26") (pin "2") (pinfunction "2_2") (pintype "passive"))
    )
    (net (code "57") (name "Net-(IC5-SDIp)") (class "Default")
      (node (ref "IC5") (pin "2") (pinfunction "SDIp_2") (pintype "input"))
      (node (ref "R24") (pin "2") (pinfunction "2_2") (pintype "passive"))
    )
    (net (code "58") (name "Net-(IC5-SDOn)") (class "Default")
      (node (ref "C34") (pin "1") (pinfunction "1_1") (pintype "passive"))
      (node (ref "IC5") (pin "10") (pinfunction "SDOn_10") (pintype "output"))
    )
    (net (code "59") (name "Net-(IC5-SDOp)") (class "Default")
      (node (ref "C30") (pin "1") (pinfunction "1_1") (pintype "passive"))
      (node (ref "IC5") (pin "11") (pinfunction "SDOp_11") (pintype "output"))
    )
    (net (code "60") (name "Net-(IC6-AmpR)") (class "Default")
      (node (ref "IC6") (pin "6") (pinfunction "AmpR_6") (pintype "input"))
      (node (ref "RAMP3") (pin "2") (pinfunction "2_2") (pintype "passive"))
    )
    (net (code "61") (name "Net-(IC6-LFI)") (class "Default")
      (node (ref "IC6") (pin "5") (pinfunction "LFI_5") (pintype "input"))
      (node (ref "R40") (pin "2") (pinfunction "2_2") (pintype "passive"))
    )
    (net (code "62") (name "Net-(IC6-RiseR)") (class "Default")
      (node (ref "IC6") (pin "7") (pinfunction "RiseR_7") (pintype "input"))
      (node (ref "RISE3") (pin "2") (pinfunction "2_2") (pintype "passive"))
    )
    (net (code "63") (name "Net-(IC6-SDIn)") (class "Default")
      (node (ref "IC6") (pin "3") (pinfunction "SDIn_3") (pintype "input"))
      (node (ref "R31") (pin "2") (pinfunction "2_2") (pintype "passive"))
    )
    (net (code "64") (name "Net-(IC6-SDIp)") (class "Default")
      (node (ref "IC6") (pin "2") (pinfunction "SDIp_2") (pintype "input"))
      (node (ref "R29") (pin "2") (pinfunction "2_2") (pintype "passive"))
    )
    (net (code "65") (name "Net-(IC6-SDOn)") (class "Default")
      (node (ref "C50") (pin "1") (pinfunction "1_1") (pintype "passive"))
      (node (ref "IC6") (pin "10") (pinfunction "SDOn_10") (pintype "output"))
    )
    (net (code "66") (name "Net-(IC6-SDOp)") (class "Default")
      (node (ref "C46") (pin "1") (pinfunction "1_1") (pintype "passive"))
      (node (ref "IC6") (pin "11") (pinfunction "SDOp_11") (pintype "output"))
    )
    (net (code "67") (name "VCC1V2") (class "Default")
      (node (ref "C23") (pin "1") (pinfunction "1_1") (pintype "passive"))
      (node (ref "C24") (pin "1") (pinfunction "1_1") (pintype "passive"))
      (node (ref "C25") (pin "1") (pinfunction "1_1") (pintype "passive"))
      (node (ref "C26") (pin "1") (pinfunction "1_1") (pintype "passive"))
      (node (ref "C39") (pin "1") (pinfunction "1_1") (pintype "passive"))
      (node (ref "C40") (pin "1") (pinfunction "1_1") (pintype "passive"))
      (node (ref "C41") (pin "1") (pinfunction "1_1") (pintype "passive"))
      (node (ref "C42") (pin "1") (pinfunction "1_1") (pintype "passive"))
      (node (ref "IC3") (pin "13") (pinfunction "VCC_13") (pintype "power_in"))
      (node (ref "IC3") (pin "16") (pinfunction "VCC_16") (pintype "power_in"))
      (node (ref "IC4") (pin "13") (pinfunction "VCC_13") (pintype "power_in"))
      (node (ref "IC4") (pin "16") (pinfunction "VCC_16") (pintype "power_in"))
      (node (ref "IC5") (pin "13") (pinfunction "VCC_13") (pintype "power_in"))
      (node (ref "IC5") (pin "16") (pinfunction "VCC_16") (pintype "power_in"))
      (node (ref "IC6") (pin "13") (pinfunction "VCC_13") (pintype "power_in"))
      (node (ref "IC6") (pin "16") (pinfunction "VCC_16") (pintype "power_in"))
      (node (ref "RAMP0") (pin "1") (pinfunction "1_1") (pintype "passive"))
      (node (ref "RAMP1") (pin "1") (pinfunction "1_1") (pintype "passive"))
      (node (ref "RAMP2") (pin "1") (pinfunction "1_1") (pintype "passive"))
      (node (ref "RAMP3") (pin "1") (pinfunction "1_1") (pintype "passive"))
      (node (ref "RISE0") (pin "1") (pinfunction "1_1") (pintype "passive"))
      (node (ref "RISE1") (pin "1") (pinfunction "1_1") (pintype "passive"))
      (node (ref "RISE2") (pin "1") (pinfunction "1_1") (pintype "passive"))
      (node (ref "RISE3") (pin "1") (pinfunction "1_1") (pintype "passive"))
    )
    (net (code "68") (name "unconnected-(IC3-NC-Pad8)") (class "Default")
      (node (ref "IC3") (pin "8") (pinfunction "NC_8") (pintype "passive+no_connect"))
    )
    (net (code "69") (name "unconnected-(IC3-NC-Pad14)") (class "Default")
      (node (ref "IC3") (pin "14") (pinfunction "NC_14") (pintype "passive+no_connect"))
    )
    (net (code "70") (name "unconnected-(IC3-NC-Pad15)") (class "Default")
      (node (ref "IC3") (pin "15") (pinfunction "NC_15") (pintype "passive+no_connect"))
    )
    (net (code "71") (name "unconnected-(IC4-NC-Pad8)") (class "Default")
      (node (ref "IC4") (pin "8") (pinfunction "NC_8") (pintype "passive+no_connect"))
    )
    (net (code "72") (name "unconnected-(IC4-NC-Pad14)") (class "Default")
      (node (ref "IC4") (pin "14") (pinfunction "NC_14") (pintype "passive+no_connect"))
    )
    (net (code "73") (name "unconnected-(IC4-NC-Pad15)") (class "Default")
      (node (ref "IC4") (pin "15") (pinfunction "NC_15") (pintype "passive+no_connect"))
    )
    (net (code "74") (name "unconnected-(IC5-NC-Pad8)") (class "Default")
      (node (ref "IC5") (pin "8") (pinfunction "NC_8") (pintype "passive+no_connect"))
    )
    (net (code "75") (name "unconnected-(IC5-NC-Pad14)") (class "Default")
      (node (ref "IC5") (pin "14") (pinfunction "NC_14") (pintype "passive+no_connect"))
    )
    (net (code "76") (name "unconnected-(IC5-NC-Pad15)") (class "Default")
      (node (ref "IC5") (pin "15") (pinfunction "NC_15") (pintype "passive+no_connect"))
    )
    (net (code "77") (name "unconnected-(IC6-NC-Pad8)") (class "Default")
      (node (ref "IC6") (pin "8") (pinfunction "NC_8") (pintype "passive+no_connect"))
    )
    (net (code "78") (name "unconnected-(IC6-NC-Pad14)") (class "Default")
      (node (ref "IC6") (pin "14") (pinfunction "NC_14") (pintype "passive+no_connect"))
    )
    (net (code "79") (name "unconnected-(IC6-NC-Pad15)") (class "Default")
      (node (ref "IC6") (pin "15") (pinfunction "NC_15") (pintype "passive+no_connect"))
    )
  )
)
